# HK0J2071758B03.net
KiCad netlist of a schematic drawn in Altium Designer
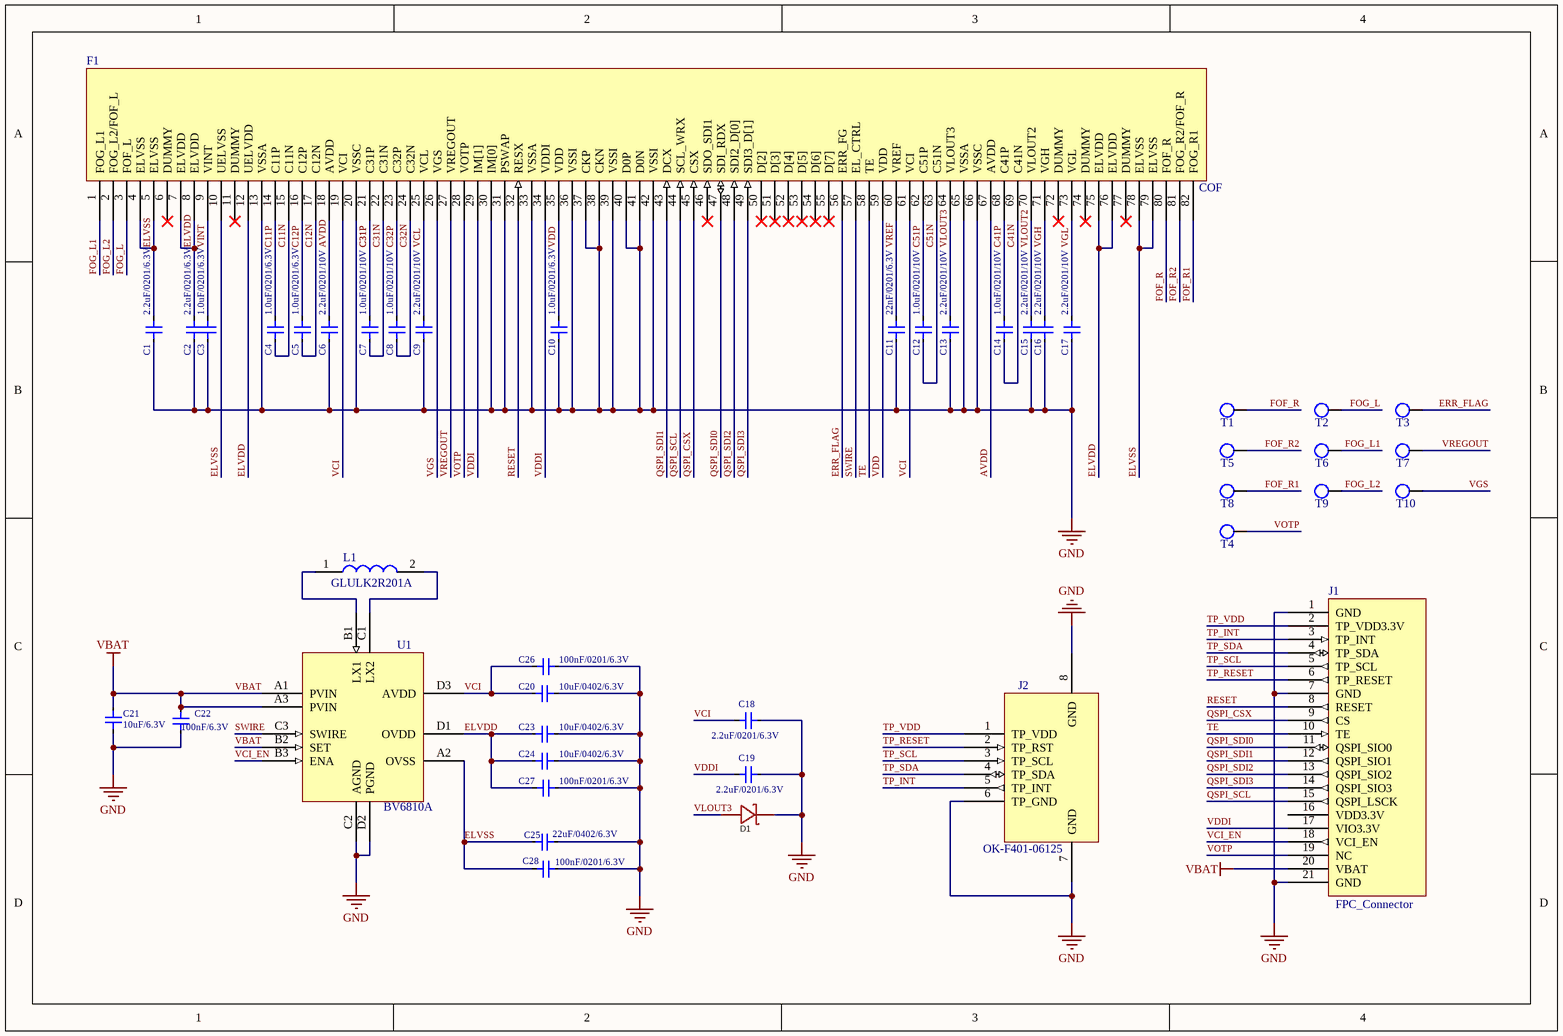
[diagram p0: HK0J2071758B03.SchDoc]

(export (version "E")
  (design (tool "Eeschema 10.0.6"))
  (components
    (comp (ref "C1")
      (value "2.2uF/0201/6.3V")
      (footprint "CAPC0603X33N")
      (description "NONE")
      (fields
        (field (name "MANUFACTURER") "Murata")
        (field (name "MANUFACTURER PART NUMBER") "GRM033R61A105ME15D")
      )
      (libsource (lib "COF") (part "Capacitor"))
    )
    (comp (ref "C2")
      (value "2.2uF/0201/6.3V")
      (footprint "CAPC0603X33N")
      (description "NONE")
      (fields
        (field (name "MANUFACTURER") "Murata")
        (field (name "MANUFACTURER PART NUMBER") "GRM033R61A105ME15D")
      )
      (libsource (lib "COF") (part "Capacitor"))
    )
    (comp (ref "C3")
      (value "1.0uF/0201/6.3V")
      (footprint "CAPC0603X33N")
      (description "NONE")
      (fields
        (field (name "MANUFACTURER") "Murata")
        (field (name "MANUFACTURER PART NUMBER") "GRM033R61A105ME15D")
      )
      (libsource (lib "COF") (part "Capacitor"))
    )
    (comp (ref "C4")
      (value "1.0uF/0201/6.3V")
      (footprint "CAPC0603X33N")
      (description "NONE")
      (fields
        (field (name "MANUFACTURER") "Murata")
        (field (name "MANUFACTURER PART NUMBER") "GRM033R61A105ME15D")
      )
      (libsource (lib "COF") (part "Capacitor"))
    )
    (comp (ref "C5")
      (value "1.0uF/0201/6.3V")
      (footprint "CAPC0603X33N")
      (description "NONE")
      (fields
        (field (name "MANUFACTURER") "Murata")
        (field (name "MANUFACTURER PART NUMBER") "GRM033R61A105ME15D")
      )
      (libsource (lib "COF") (part "Capacitor"))
    )
    (comp (ref "C6")
      (value "2.2uF/0201/10V")
      (footprint "CAPC0603X33N")
      (description "NONE")
      (fields
        (field (name "MANUFACTURER") "Murata")
        (field (name "MANUFACTURER PART NUMBER") "GRM033R61A105ME15D")
      )
      (libsource (lib "COF") (part "Capacitor"))
    )
    (comp (ref "C7")
      (value "1.0uF/0201/10V")
      (footprint "CAPC0603X33N")
      (description "NONE")
      (fields
        (field (name "MANUFACTURER") "Murata")
        (field (name "MANUFACTURER PART NUMBER") "GRM033R61A105ME15D")
      )
      (libsource (lib "COF") (part "Capacitor"))
    )
    (comp (ref "C8")
      (value "1.0uF/0201/10V")
      (footprint "CAPC0603X33N")
      (description "NONE")
      (fields
        (field (name "MANUFACTURER") "Murata")
        (field (name "MANUFACTURER PART NUMBER") "GRM033R61A105ME15D")
      )
      (libsource (lib "COF") (part "Capacitor"))
    )
    (comp (ref "C9")
      (value "2.2uF/0201/10V")
      (footprint "CAPC0603X33N")
      (description "NONE")
      (fields
        (field (name "MANUFACTURER") "Murata")
        (field (name "MANUFACTURER PART NUMBER") "GRM033R61A105ME15D")
      )
      (libsource (lib "COF") (part "Capacitor"))
    )
    (comp (ref "C10")
      (value "1.0uF/0201/6.3V")
      (footprint "CAPC0603X33N")
      (description "NONE")
      (fields
        (field (name "MANUFACTURER") "Murata")
        (field (name "MANUFACTURER PART NUMBER") "GRM033R61A105ME15D")
      )
      (libsource (lib "COF") (part "Capacitor"))
    )
    (comp (ref "C11")
      (value "22nF/0201/6.3V")
      (footprint "CAPC0603X33N")
      (description "NONE")
      (fields
        (field (name "MANUFACTURER") "Murata")
        (field (name "MANUFACTURER PART NUMBER") "GRM033R61A105ME15D")
      )
      (libsource (lib "COF") (part "Capacitor"))
    )
    (comp (ref "C12")
      (value "1.0uF/0201/10V")
      (footprint "CAPC0603X33N")
      (description "NONE")
      (fields
        (field (name "MANUFACTURER") "Murata")
        (field (name "MANUFACTURER PART NUMBER") "GRM033R61A105ME15D")
      )
      (libsource (lib "COF") (part "Capacitor"))
    )
    (comp (ref "C13")
      (value "2.2uF/0201/10V")
      (footprint "CAPC0603X33N")
      (description "NONE")
      (fields
        (field (name "MANUFACTURER") "Murata")
        (field (name "MANUFACTURER PART NUMBER") "GRM033R61A105ME15D")
      )
      (libsource (lib "COF") (part "Capacitor"))
    )
    (comp (ref "C14")
      (value "1.0uF/0201/10V")
      (footprint "CAPC0603X33N")
      (description "NONE")
      (fields
        (field (name "MANUFACTURER") "Murata")
        (field (name "MANUFACTURER PART NUMBER") "GRM033R61A105ME15D")
      )
      (libsource (lib "COF") (part "Capacitor"))
    )
    (comp (ref "C15")
      (value "2.2uF/0201/10V")
      (footprint "CAPC0603X33N")
      (description "NONE")
      (fields
        (field (name "MANUFACTURER") "Murata")
        (field (name "MANUFACTURER PART NUMBER") "GRM033R61A105ME15D")
      )
      (libsource (lib "COF") (part "Capacitor"))
    )
    (comp (ref "C16")
      (value "2.2uF/0201/10V")
      (footprint "CAPC0603X33N")
      (description "NONE")
      (fields
        (field (name "MANUFACTURER") "Murata")
        (field (name "MANUFACTURER PART NUMBER") "GRM033R61A105ME15D")
      )
      (libsource (lib "COF") (part "Capacitor"))
    )
    (comp (ref "C17")
      (value "2.2uF/0201/10V")
      (footprint "CAPC0603X33N")
      (description "NONE")
      (fields
        (field (name "MANUFACTURER") "Murata")
        (field (name "MANUFACTURER PART NUMBER") "GRM033R61A105ME15D")
      )
      (libsource (lib "COF") (part "Capacitor"))
    )
    (comp (ref "C18")
      (value "2.2uF/0201/6.3V")
      (footprint "CAPC0603X33N")
      (description "NONE")
      (fields
        (field (name "MANUFACTURER") "Murata")
        (field (name "MANUFACTURER PART NUMBER") "GRM033R61A105ME15D")
      )
      (libsource (lib "COF") (part "Capacitor"))
    )
    (comp (ref "C19")
      (value "2.2uF/0201/6.3V")
      (footprint "CAPC0603X33N")
      (description "NONE")
      (fields
        (field (name "MANUFACTURER") "Murata")
        (field (name "MANUFACTURER PART NUMBER") "GRM033R61A105ME15D")
      )
      (libsource (lib "COF") (part "Capacitor"))
    )
    (comp (ref "C20")
      (value "10uF/0402/6.3V")
      (footprint "CAPC1005X57N")
      (description "NONE")
      (fields
        (field (name "MANUFACTURER") "Murata")
        (field (name "MANUFACTURER PART NUMBER") "GRM033R61A105ME15D")
      )
      (libsource (lib "COF") (part "Capacitor"))
    )
    (comp (ref "C21")
      (value "10uF/6.3V")
      (footprint "CAPC1005X57N")
      (description "NONE")
      (fields
        (field (name "MANUFACTURER") "Murata")
        (field (name "MANUFACTURER PART NUMBER") "GRM033R61A105ME15D")
      )
      (libsource (lib "COF") (part "Capacitor"))
    )
    (comp (ref "C22")
      (value "100nF/6.3V")
      (footprint "CAPC0603X33N")
      (description "NONE")
      (fields
        (field (name "MANUFACTURER") "Murata")
        (field (name "MANUFACTURER PART NUMBER") "GRM033R61A105ME15D")
      )
      (libsource (lib "COF") (part "Capacitor"))
    )
    (comp (ref "C23")
      (value "10uF/0402/6.3V")
      (footprint "CAPC1005X57N")
      (description "NONE")
      (fields
        (field (name "MANUFACTURER") "Murata")
        (field (name "MANUFACTURER PART NUMBER") "GRM033R61A105ME15D")
      )
      (libsource (lib "COF") (part "Capacitor"))
    )
    (comp (ref "C24")
      (value "10uF/0402/6.3V")
      (footprint "CAPC1005X57N")
      (description "NONE")
      (fields
        (field (name "MANUFACTURER") "Murata")
        (field (name "MANUFACTURER PART NUMBER") "GRM033R61A105ME15D")
      )
      (libsource (lib "COF") (part "Capacitor"))
    )
    (comp (ref "C25")
      (value "22uF/0402/6.3V")
      (footprint "CAPC1005X57N")
      (description "NONE")
      (fields
        (field (name "MANUFACTURER") "Murata")
        (field (name "MANUFACTURER PART NUMBER") "GRM033R61A105ME15D")
      )
      (libsource (lib "COF") (part "Capacitor"))
    )
    (comp (ref "C26")
      (value "100nF/0201/6.3V")
      (footprint "CAPC0603X33N")
      (description "NONE")
      (fields
        (field (name "MANUFACTURER") "Murata")
        (field (name "MANUFACTURER PART NUMBER") "GRM033R61A105ME15D")
      )
      (libsource (lib "COF") (part "Capacitor"))
    )
    (comp (ref "C27")
      (value "100nF/0201/6.3V")
      (footprint "CAPC0603X33N")
      (description "NONE")
      (fields
        (field (name "MANUFACTURER") "Murata")
        (field (name "MANUFACTURER PART NUMBER") "GRM033R61A105ME15D")
      )
      (libsource (lib "COF") (part "Capacitor"))
    )
    (comp (ref "C28")
      (value "100nF/0201/6.3V")
      (footprint "CAPC0603X33N")
      (description "NONE")
      (fields
        (field (name "MANUFACTURER") "Murata")
        (field (name "MANUFACTURER PART NUMBER") "GRM033R61A105ME15D")
      )
      (libsource (lib "COF") (part "Capacitor"))
    )
    (comp (ref "D1")
      (value "LDSR01S30ST5G")
      (footprint "DFN0603-D_L0.6-W0.3-P0.34-RD")
      (fields (field (name "MANUFACTURER") "LRC(乐山无线电)"))
      (libsource (lib "COF") (part "LDSR01S30ST5G"))
    )
    (comp (ref "F1") (value "COF") (footprint "COF Connector") (libsource (lib "COF") (part "COF")))
    (comp (ref "J1")
      (value "FPC_Connector")
      (footprint "FPC Connector")
      (libsource (lib "COF") (part "21Pin_Connector"))
    )
    (comp (ref "J2")
      (value "OK-F401-06125")
      (footprint "FFC-SMD_6P-P0.50_FH34SRJ-6S-0.5SH")
      (libsource (lib "COF") (part "OK-F401-06125"))
    )
    (comp (ref "L1")
      (value "GLULK2R201A")
      (footprint "MPL2012S2R2MDT")
      (description "Inductor")
      (fields
        (field (name "MANUFACTURER_PART_NUMBER") "LQM2MPN2R2NG0L")
        (field (name "MOUSER PART NUMBER") "81-LQM2MPN2R2NG0L")
      )
      (libsource (lib "COF") (part "GLULK2R201A"))
    )
    (comp (ref "T1")
      (value "Test_Point")
      (footprint "TP-C045-PI")
      (libsource (lib "COF") (part "Test_Point"))
    )
    (comp (ref "T2")
      (value "Test_Point")
      (footprint "TP-C045-PI")
      (libsource (lib "COF") (part "Test_Point"))
    )
    (comp (ref "T3")
      (value "Test_Point")
      (footprint "TP-C045-PI")
      (libsource (lib "COF") (part "Test_Point"))
    )
    (comp (ref "T4")
      (value "Test_Point")
      (footprint "TP-C045-PI")
      (libsource (lib "COF") (part "Test_Point"))
    )
    (comp (ref "T5")
      (value "Test_Point")
      (footprint "TP-C045-PI")
      (libsource (lib "COF") (part "Test_Point"))
    )
    (comp (ref "T6")
      (value "Test_Point")
      (footprint "TP-C045-PI")
      (libsource (lib "COF") (part "Test_Point"))
    )
    (comp (ref "T7")
      (value "Test_Point")
      (footprint "TP-C045-PI")
      (libsource (lib "COF") (part "Test_Point"))
    )
    (comp (ref "T8")
      (value "Test_Point")
      (footprint "TP-C045-PI")
      (libsource (lib "COF") (part "Test_Point"))
    )
    (comp (ref "T9")
      (value "Test_Point")
      (footprint "TP-C045-PI")
      (libsource (lib "COF") (part "Test_Point"))
    )
    (comp (ref "T10")
      (value "Test_Point")
      (footprint "TP-C045-PI")
      (libsource (lib "COF") (part "Test_Point"))
    )
    (comp (ref "U1")
      (value "BV6810A")
      (footprint "WLCSP-12_L1.7-W1.5-R4-C3-P0.40-TL-1")
      (libsource (lib "COF") (part "BV6810A"))
    )
  )
  (nets
    (net (code "1") (name "/AVDD") (class "Default")
      (node (ref "C6") (pin "1") (pinfunction "1_1") (pintype "passive"))
      (node (ref "F1") (pin "18") (pinfunction "AVDD_18") (pintype "power_in"))
      (node (ref "F1") (pin "67") (pinfunction "AVDD_67") (pintype "power_in"))
    )
    (net (code "2") (name "/C11N") (class "Default")
      (node (ref "C4") (pin "2") (pinfunction "2_2") (pintype "passive"))
      (node (ref "F1") (pin "15") (pinfunction "C11N_15") (pintype "tri_state"))
    )
    (net (code "3") (name "/C11P") (class "Default")
      (node (ref "C4") (pin "1") (pinfunction "1_1") (pintype "passive"))
      (node (ref "F1") (pin "14") (pinfunction "C11P_14") (pintype "tri_state"))
    )
    (net (code "4") (name "/C12N") (class "Default")
      (node (ref "C5") (pin "2") (pinfunction "2_2") (pintype "passive"))
      (node (ref "F1") (pin "17") (pinfunction "C12N_17") (pintype "tri_state"))
    )
    (net (code "5") (name "/C12P") (class "Default")
      (node (ref "C5") (pin "1") (pinfunction "1_1") (pintype "passive"))
      (node (ref "F1") (pin "16") (pinfunction "C12P_16") (pintype "tri_state"))
    )
    (net (code "6") (name "/C31N") (class "Default")
      (node (ref "C7") (pin "2") (pinfunction "2_2") (pintype "passive"))
      (node (ref "F1") (pin "22") (pinfunction "C31N_22") (pintype "tri_state"))
    )
    (net (code "7") (name "/C31P") (class "Default")
      (node (ref "C7") (pin "1") (pinfunction "1_1") (pintype "passive"))
      (node (ref "F1") (pin "21") (pinfunction "C31P_21") (pintype "tri_state"))
    )
    (net (code "8") (name "/C32N") (class "Default")
      (node (ref "C8") (pin "2") (pinfunction "2_2") (pintype "passive"))
      (node (ref "F1") (pin "24") (pinfunction "C32N_24") (pintype "tri_state"))
    )
    (net (code "9") (name "/C32P") (class "Default")
      (node (ref "C8") (pin "1") (pinfunction "1_1") (pintype "passive"))
      (node (ref "F1") (pin "23") (pinfunction "C32P_23") (pintype "tri_state"))
    )
    (net (code "10") (name "/C41N") (class "Default")
      (node (ref "C14") (pin "2") (pinfunction "2_2") (pintype "passive"))
      (node (ref "F1") (pin "69") (pinfunction "C41N_69") (pintype "tri_state"))
    )
    (net (code "11") (name "/C41P") (class "Default")
      (node (ref "C14") (pin "1") (pinfunction "1_1") (pintype "passive"))
      (node (ref "F1") (pin "68") (pinfunction "C41P_68") (pintype "tri_state"))
    )
    (net (code "12") (name "/C51N") (class "Default")
      (node (ref "C12") (pin "2") (pinfunction "2_2") (pintype "passive"))
      (node (ref "F1") (pin "63") (pinfunction "C51N_63") (pintype "tri_state"))
    )
    (net (code "13") (name "/C51P") (class "Default")
      (node (ref "C12") (pin "1") (pinfunction "1_1") (pintype "passive"))
      (node (ref "F1") (pin "62") (pinfunction "C51P_62") (pintype "tri_state"))
    )
    (net (code "14") (name "/ELVDD") (class "Default")
      (node (ref "C2") (pin "1") (pinfunction "1_1") (pintype "passive"))
      (node (ref "C23") (pin "2") (pinfunction "2_2") (pintype "passive"))
      (node (ref "C24") (pin "2") (pinfunction "2_2") (pintype "passive"))
      (node (ref "C27") (pin "1") (pinfunction "1_1") (pintype "passive"))
      (node (ref "F1") (pin "12") (pinfunction "UELVDD_12") (pintype "power_in"))
      (node (ref "F1") (pin "7") (pinfunction "ELVDD_7") (pintype "power_in"))
      (node (ref "F1") (pin "75") (pinfunction "ELVDD_75") (pintype "power_in"))
      (node (ref "F1") (pin "76") (pinfunction "ELVDD_76") (pintype "power_in"))
      (node (ref "F1") (pin "8") (pinfunction "ELVDD_8") (pintype "power_in"))
      (node (ref "U1") (pin "D1") (pinfunction "OVDD_D1") (pintype "power_in"))
    )
    (net (code "15") (name "/ELVSS") (class "Default")
      (node (ref "C1") (pin "1") (pinfunction "1_1") (pintype "passive"))
      (node (ref "C25") (pin "2") (pinfunction "2_2") (pintype "passive"))
      (node (ref "C28") (pin "1") (pinfunction "1_1") (pintype "passive"))
      (node (ref "F1") (pin "10") (pinfunction "UELVSS_10") (pintype "power_in"))
      (node (ref "F1") (pin "4") (pinfunction "ELVSS_4") (pintype "power_in"))
      (node (ref "F1") (pin "5") (pinfunction "ELVSS_5") (pintype "power_in"))
      (node (ref "F1") (pin "78") (pinfunction "ELVSS_78") (pintype "power_in"))
      (node (ref "F1") (pin "79") (pinfunction "ELVSS_79") (pintype "power_in"))
      (node (ref "U1") (pin "A2") (pinfunction "OVSS_A2") (pintype "power_in"))
    )
    (net (code "16") (name "/ERR_FLAG") (class "Default")
      (node (ref "F1") (pin "56") (pinfunction "ERR_FG_56") (pintype "tri_state"))
      (node (ref "T3") (pin "1") (pinfunction "1_1") (pintype "passive"))
    )
    (net (code "17") (name "/FOF_R") (class "Default")
      (node (ref "F1") (pin "80") (pinfunction "FOF_R_80") (pintype "tri_state"))
      (node (ref "T1") (pin "1") (pinfunction "1_1") (pintype "passive"))
    )
    (net (code "18") (name "/FOF_R1") (class "Default")
      (node (ref "F1") (pin "82") (pinfunction "FOG_R1_82") (pintype "tri_state"))
      (node (ref "T8") (pin "1") (pinfunction "1_1") (pintype "passive"))
    )
    (net (code "19") (name "/FOF_R2") (class "Default")
      (node (ref "F1") (pin "81") (pinfunction "FOG_R2/FOF_R_81") (pintype "tri_state"))
      (node (ref "T5") (pin "1") (pinfunction "1_1") (pintype "passive"))
    )
    (net (code "20") (name "/FOG_L") (class "Default")
      (node (ref "F1") (pin "3") (pinfunction "FOF_L_3") (pintype "tri_state"))
      (node (ref "T2") (pin "1") (pinfunction "1_1") (pintype "passive"))
    )
    (net (code "21") (name "/FOG_L1") (class "Default")
      (node (ref "F1") (pin "1") (pinfunction "FOG_L1_1") (pintype "tri_state"))
      (node (ref "T6") (pin "1") (pinfunction "1_1") (pintype "passive"))
    )
    (net (code "22") (name "/FOG_L2") (class "Default")
      (node (ref "F1") (pin "2") (pinfunction "FOG_L2/FOF_L_2") (pintype "tri_state"))
      (node (ref "T9") (pin "1") (pinfunction "1_1") (pintype "passive"))
    )
    (net (code "23") (name "/QSPI_CSX") (class "Default")
      (node (ref "F1") (pin "45") (pinfunction "CSX_45") (pintype "input"))
      (node (ref "J1") (pin "9") (pinfunction "CS_9") (pintype "output"))
    )
    (net (code "24") (name "/QSPI_SCL") (class "Default")
      (node (ref "F1") (pin "44") (pinfunction "SCL_WRX_44") (pintype "input"))
      (node (ref "J1") (pin "15") (pinfunction "QSPI_LSCK_15") (pintype "output"))
    )
    (net (code "25") (name "/QSPI_SDI0") (class "Default")
      (node (ref "F1") (pin "47") (pinfunction "SDI_RDX_47") (pintype "bidirectional"))
      (node (ref "J1") (pin "11") (pinfunction "QSPI_SIO0_11") (pintype "bidirectional"))
    )
    (net (code "26") (name "/QSPI_SDI1") (class "Default")
      (node (ref "F1") (pin "43") (pinfunction "DCX_43") (pintype "input"))
      (node (ref "J1") (pin "12") (pinfunction "QSPI_SIO1_12") (pintype "output"))
    )
    (net (code "27") (name "/QSPI_SDI2") (class "Default")
      (node (ref "F1") (pin "48") (pinfunction "SDI2_D[0]_48") (pintype "input"))
      (node (ref "J1") (pin "13") (pinfunction "QSPI_SIO2_13") (pintype "output"))
    )
    (net (code "28") (name "/QSPI_SDI3") (class "Default")
      (node (ref "F1") (pin "49") (pinfunction "SDI3_D[1]_49") (pintype "input"))
      (node (ref "J1") (pin "14") (pinfunction "QSPI_SIO3_14") (pintype "output"))
    )
    (net (code "29") (name "/RESET") (class "Default")
      (node (ref "F1") (pin "32") (pinfunction "RESX_32") (pintype "input"))
      (node (ref "J1") (pin "8") (pinfunction "RESET_8") (pintype "output"))
    )
    (net (code "30") (name "/SWIRE") (class "Default")
      (node (ref "F1") (pin "57") (pinfunction "EL_CTRL_57") (pintype "tri_state"))
      (node (ref "U1") (pin "C3") (pinfunction "SWIRE_C3") (pintype "input"))
    )
    (net (code "31") (name "/TE") (class "Default")
      (node (ref "F1") (pin "58") (pinfunction "TE_58") (pintype "tri_state"))
      (node (ref "J1") (pin "10") (pinfunction "TE_10") (pintype "input"))
    )
    (net (code "32") (name "/TP_INT") (class "Default")
      (node (ref "J1") (pin "3") (pinfunction "TP_INT_3") (pintype "input"))
      (node (ref "J2") (pin "5") (pinfunction "TP_INT_5") (pintype "output"))
    )
    (net (code "33") (name "/TP_RESET") (class "Default")
      (node (ref "J1") (pin "6") (pinfunction "TP_RESET_6") (pintype "output"))
      (node (ref "J2") (pin "2") (pinfunction "TP_RST_2") (pintype "input"))
    )
    (net (code "34") (name "/TP_SCL") (class "Default")
      (node (ref "J1") (pin "5") (pinfunction "TP_SCL_5") (pintype "output"))
      (node (ref "J2") (pin "3") (pinfunction "TP_SCL_3") (pintype "input"))
    )
    (net (code "35") (name "/TP_SDA") (class "Default")
      (node (ref "J1") (pin "4") (pinfunction "TP_SDA_4") (pintype "bidirectional"))
      (node (ref "J2") (pin "4") (pinfunction "TP_SDA_4") (pintype "bidirectional"))
    )
    (net (code "36") (name "/TP_VDD") (class "Default")
      (node (ref "J1") (pin "2") (pinfunction "TP_VDD3.3V_2") (pintype "power_in"))
      (node (ref "J2") (pin "1") (pinfunction "TP_VDD_1") (pintype "power_in"))
    )
    (net (code "37") (name "/VCI") (class "Default")
      (node (ref "C18") (pin "1") (pinfunction "1_1") (pintype "passive"))
      (node (ref "C20") (pin "2") (pinfunction "2_2") (pintype "passive"))
      (node (ref "C26") (pin "1") (pinfunction "1_1") (pintype "passive"))
      (node (ref "F1") (pin "19") (pinfunction "VCI_19") (pintype "power_in"))
      (node (ref "F1") (pin "61") (pinfunction "VCI_61") (pintype "power_in"))
      (node (ref "U1") (pin "D3") (pinfunction "AVDD_D3") (pintype "power_in"))
    )
    (net (code "38") (name "/VCI_EN") (class "Default")
      (node (ref "J1") (pin "18") (pinfunction "VCI_EN_18") (pintype "output"))
      (node (ref "U1") (pin "B3") (pinfunction "ENA_B3") (pintype "input"))
    )
    (net (code "39") (name "/VCL") (class "Default")
      (node (ref "C9") (pin "1") (pinfunction "1_1") (pintype "passive"))
      (node (ref "F1") (pin "25") (pinfunction "VCL_25") (pintype "power_in"))
    )
    (net (code "40") (name "/VDD") (class "Default")
      (node (ref "C10") (pin "1") (pinfunction "1_1") (pintype "passive"))
      (node (ref "F1") (pin "35") (pinfunction "VDD_35") (pintype "power_in"))
      (node (ref "F1") (pin "59") (pinfunction "VDD_59") (pintype "power_in"))
    )
    (net (code "41") (name "/VDDI") (class "Default")
      (node (ref "C19") (pin "1") (pinfunction "1_1") (pintype "passive"))
      (node (ref "F1") (pin "29") (pinfunction "IM[1]_29") (pintype "passive"))
      (node (ref "F1") (pin "34") (pinfunction "VDDI_34") (pintype "power_in"))
      (node (ref "J1") (pin "17") (pinfunction "VIO3.3V_17") (pintype "power_in"))
    )
    (net (code "42") (name "/VGH") (class "Default")
      (node (ref "C16") (pin "1") (pinfunction "1_1") (pintype "passive"))
      (node (ref "F1") (pin "71") (pinfunction "VGH_71") (pintype "tri_state"))
    )
    (net (code "43") (name "/VGL") (class "Default")
      (node (ref "C17") (pin "1") (pinfunction "1_1") (pintype "passive"))
      (node (ref "F1") (pin "73") (pinfunction "VGL_73") (pintype "power_in"))
    )
    (net (code "44") (name "/VGS") (class "Default")
      (node (ref "F1") (pin "26") (pinfunction "VGS_26") (pintype "power_in"))
      (node (ref "T10") (pin "1") (pinfunction "1_1") (pintype "passive"))
    )
    (net (code "45") (name "/VINT") (class "Default")
      (node (ref "C3") (pin "1") (pinfunction "1_1") (pintype "passive"))
      (node (ref "F1") (pin "9") (pinfunction "VINT_9") (pintype "tri_state"))
    )
    (net (code "46") (name "/VLOUT2") (class "Default")
      (node (ref "C15") (pin "1") (pinfunction "1_1") (pintype "passive"))
      (node (ref "F1") (pin "70") (pinfunction "VLOUT2_70") (pintype "power_in"))
    )
    (net (code "47") (name "/VLOUT3") (class "Default")
      (node (ref "C13") (pin "1") (pinfunction "1_1") (pintype "passive"))
      (node (ref "D1") (pin "2") (pinfunction "A_2") (pintype "passive"))
      (node (ref "F1") (pin "64") (pinfunction "VLOUT3_64") (pintype "power_in"))
    )
    (net (code "48") (name "/VOTP") (class "Default")
      (node (ref "F1") (pin "28") (pinfunction "VOTP_28") (pintype "power_in"))
      (node (ref "J1") (pin "19") (pinfunction "NC_19") (pintype "passive"))
      (node (ref "T4") (pin "1") (pinfunction "1_1") (pintype "passive"))
    )
    (net (code "49") (name "/VREF") (class "Default")
      (node (ref "C11") (pin "1") (pinfunction "1_1") (pintype "passive"))
      (node (ref "F1") (pin "60") (pinfunction "VREF_60") (pintype "power_in"))
    )
    (net (code "50") (name "/VREGOUT") (class "Default")
      (node (ref "F1") (pin "27") (pinfunction "VREGOUT_27") (pintype "power_in"))
      (node (ref "T7") (pin "1") (pinfunction "1_1") (pintype "passive"))
    )
    (net (code "51") (name "GND") (class "Default")
      (node (ref "C1") (pin "2") (pinfunction "2_2") (pintype "passive"))
      (node (ref "C10") (pin "2") (pinfunction "2_2") (pintype "passive"))
      (node (ref "C11") (pin "2") (pinfunction "2_2") (pintype "passive"))
      (node (ref "C13") (pin "2") (pinfunction "2_2") (pintype "passive"))
      (node (ref "C15") (pin "2") (pinfunction "2_2") (pintype "passive"))
      (node (ref "C16") (pin "2") (pinfunction "2_2") (pintype "passive"))
      (node (ref "C17") (pin "2") (pinfunction "2_2") (pintype "passive"))
      (node (ref "C18") (pin "2") (pinfunction "2_2") (pintype "passive"))
      (node (ref "C19") (pin "2") (pinfunction "2_2") (pintype "passive"))
      (node (ref "C2") (pin "2") (pinfunction "2_2") (pintype "passive"))
      (node (ref "C20") (pin "1") (pinfunction "1_1") (pintype "passive"))
      (node (ref "C21") (pin "1") (pinfunction "1_1") (pintype "passive"))
      (node (ref "C22") (pin "2") (pinfunction "2_2") (pintype "passive"))
      (node (ref "C23") (pin "1") (pinfunction "1_1") (pintype "passive"))
      (node (ref "C24") (pin "1") (pinfunction "1_1") (pintype "passive"))
      (node (ref "C25") (pin "1") (pinfunction "1_1") (pintype "passive"))
      (node (ref "C26") (pin "2") (pinfunction "2_2") (pintype "passive"))
      (node (ref "C27") (pin "2") (pinfunction "2_2") (pintype "passive"))
      (node (ref "C28") (pin "2") (pinfunction "2_2") (pintype "passive"))
      (node (ref "C3") (pin "2") (pinfunction "2_2") (pintype "passive"))
      (node (ref "C6") (pin "2") (pinfunction "2_2") (pintype "passive"))
      (node (ref "C9") (pin "2") (pinfunction "2_2") (pintype "passive"))
      (node (ref "D1") (pin "1") (pinfunction "C_1") (pintype "passive"))
      (node (ref "F1") (pin "13") (pinfunction "VSSA_13") (pintype "power_in"))
      (node (ref "F1") (pin "20") (pinfunction "VSSC_20") (pintype "power_in"))
      (node (ref "F1") (pin "30") (pinfunction "IM[0]_30") (pintype "passive"))
      (node (ref "F1") (pin "31") (pinfunction "PSWAP_31") (pintype "passive"))
      (node (ref "F1") (pin "33") (pinfunction "VSSA_33") (pintype "power_in"))
      (node (ref "F1") (pin "36") (pinfunction "VSSI_36") (pintype "power_in"))
      (node (ref "F1") (pin "37") (pinfunction "CKP_37") (pintype "passive"))
      (node (ref "F1") (pin "38") (pinfunction "CKN_38") (pintype "passive"))
      (node (ref "F1") (pin "39") (pinfunction "VSSI_39") (pintype "power_in"))
      (node (ref "F1") (pin "40") (pinfunction "D0P_40") (pintype "passive"))
      (node (ref "F1") (pin "41") (pinfunction "D0N_41") (pintype "passive"))
      (node (ref "F1") (pin "42") (pinfunction "VSSI_42") (pintype "power_in"))
      (node (ref "F1") (pin "65") (pinfunction "VSSA_65") (pintype "power_in"))
      (node (ref "F1") (pin "66") (pinfunction "VSSC_66") (pintype "power_in"))
      (node (ref "J1") (pin "1") (pinfunction "GND_1") (pintype "power_in"))
      (node (ref "J1") (pin "21") (pinfunction "GND_21") (pintype "power_in"))
      (node (ref "J1") (pin "7") (pinfunction "GND_7") (pintype "power_in"))
      (node (ref "J2") (pin "6") (pinfunction "TP_GND_6") (pintype "power_in"))
      (node (ref "J2") (pin "7") (pinfunction "GND_7") (pintype "power_in"))
      (node (ref "J2") (pin "8") (pinfunction "GND_8") (pintype "power_in"))
      (node (ref "U1") (pin "C2") (pinfunction "AGND_C2") (pintype "power_in"))
      (node (ref "U1") (pin "D2") (pinfunction "PGND_D2") (pintype "power_in"))
    )
    (net (code "52") (name "Net-(U1-LX1)") (class "Default")
      (node (ref "L1") (pin "1") (pinfunction "1_1") (pintype "passive"))
      (node (ref "U1") (pin "B1") (pinfunction "LX1_B1") (pintype "input"))
    )
    (net (code "53") (name "Net-(U1-LX2)") (class "Default")
      (node (ref "L1") (pin "2") (pinfunction "2_2") (pintype "passive"))
      (node (ref "U1") (pin "C1") (pinfunction "LX2_C1") (pintype "tri_state"))
    )
    (net (code "54") (name "VBAT") (class "Default")
      (node (ref "C21") (pin "2") (pinfunction "2_2") (pintype "passive"))
      (node (ref "C22") (pin "1") (pinfunction "1_1") (pintype "passive"))
      (node (ref "J1") (pin "20") (pinfunction "VBAT_20") (pintype "power_in"))
      (node (ref "U1") (pin "A1") (pinfunction "PVIN_A1") (pintype "power_in"))
      (node (ref "U1") (pin "A3") (pinfunction "PVIN_A3") (pintype "power_in"))
      (node (ref "U1") (pin "B2") (pinfunction "SET_B2") (pintype "input"))
    )
    (net (code "55") (name "unconnected-(F1-DUMMY-Pad6)") (class "Default")
      (node (ref "F1") (pin "6") (pinfunction "DUMMY_6") (pintype "tri_state+no_connect"))
    )
    (net (code "56") (name "unconnected-(F1-DUMMY-Pad11)") (class "Default")
      (node (ref "F1") (pin "11") (pinfunction "DUMMY_11") (pintype "tri_state+no_connect"))
    )
    (net (code "57") (name "unconnected-(F1-DUMMY-Pad72)") (class "Default")
      (node (ref "F1") (pin "72") (pinfunction "DUMMY_72") (pintype "tri_state+no_connect"))
    )
    (net (code "58") (name "unconnected-(F1-DUMMY-Pad74)") (class "Default")
      (node (ref "F1") (pin "74") (pinfunction "DUMMY_74") (pintype "tri_state+no_connect"))
    )
    (net (code "59") (name "unconnected-(F1-DUMMY-Pad77)") (class "Default")
      (node (ref "F1") (pin "77") (pinfunction "DUMMY_77") (pintype "tri_state+no_connect"))
    )
    (net (code "60") (name "unconnected-(F1-D[2]-Pad50)") (class "Default")
      (node (ref "F1") (pin "50") (pinfunction "D[2]_50") (pintype "tri_state+no_connect"))
    )
    (net (code "61") (name "unconnected-(F1-D[3]-Pad51)") (class "Default")
      (node (ref "F1") (pin "51") (pinfunction "D[3]_51") (pintype "tri_state+no_connect"))
    )
    (net (code "62") (name "unconnected-(F1-D[4]-Pad52)") (class "Default")
      (node (ref "F1") (pin "52") (pinfunction "D[4]_52") (pintype "tri_state+no_connect"))
    )
    (net (code "63") (name "unconnected-(F1-D[5]-Pad53)") (class "Default")
      (node (ref "F1") (pin "53") (pinfunction "D[5]_53") (pintype "tri_state+no_connect"))
    )
    (net (code "64") (name "unconnected-(F1-D[6]-Pad54)") (class "Default")
      (node (ref "F1") (pin "54") (pinfunction "D[6]_54") (pintype "tri_state+no_connect"))
    )
    (net (code "65") (name "unconnected-(F1-D[7]-Pad55)") (class "Default")
      (node (ref "F1") (pin "55") (pinfunction "D[7]_55") (pintype "tri_state+no_connect"))
    )
    (net (code "66") (name "unconnected-(F1-SDO_SDI1-Pad46)") (class "Default")
      (node (ref "F1") (pin "46") (pinfunction "SDO_SDI1_46") (pintype "input+no_connect"))
    )
    (net (code "67") (name "unconnected-(J1-VDD3.3V-Pad16)") (class "Default")
      (node (ref "J1") (pin "16") (pinfunction "VDD3.3V_16") (pintype "power_in"))
    )
  )
)
